# SCH_hdzero_analog_module_slim_2023-08-07.net
KiCad netlist of a schematic drawn in EasyEDA
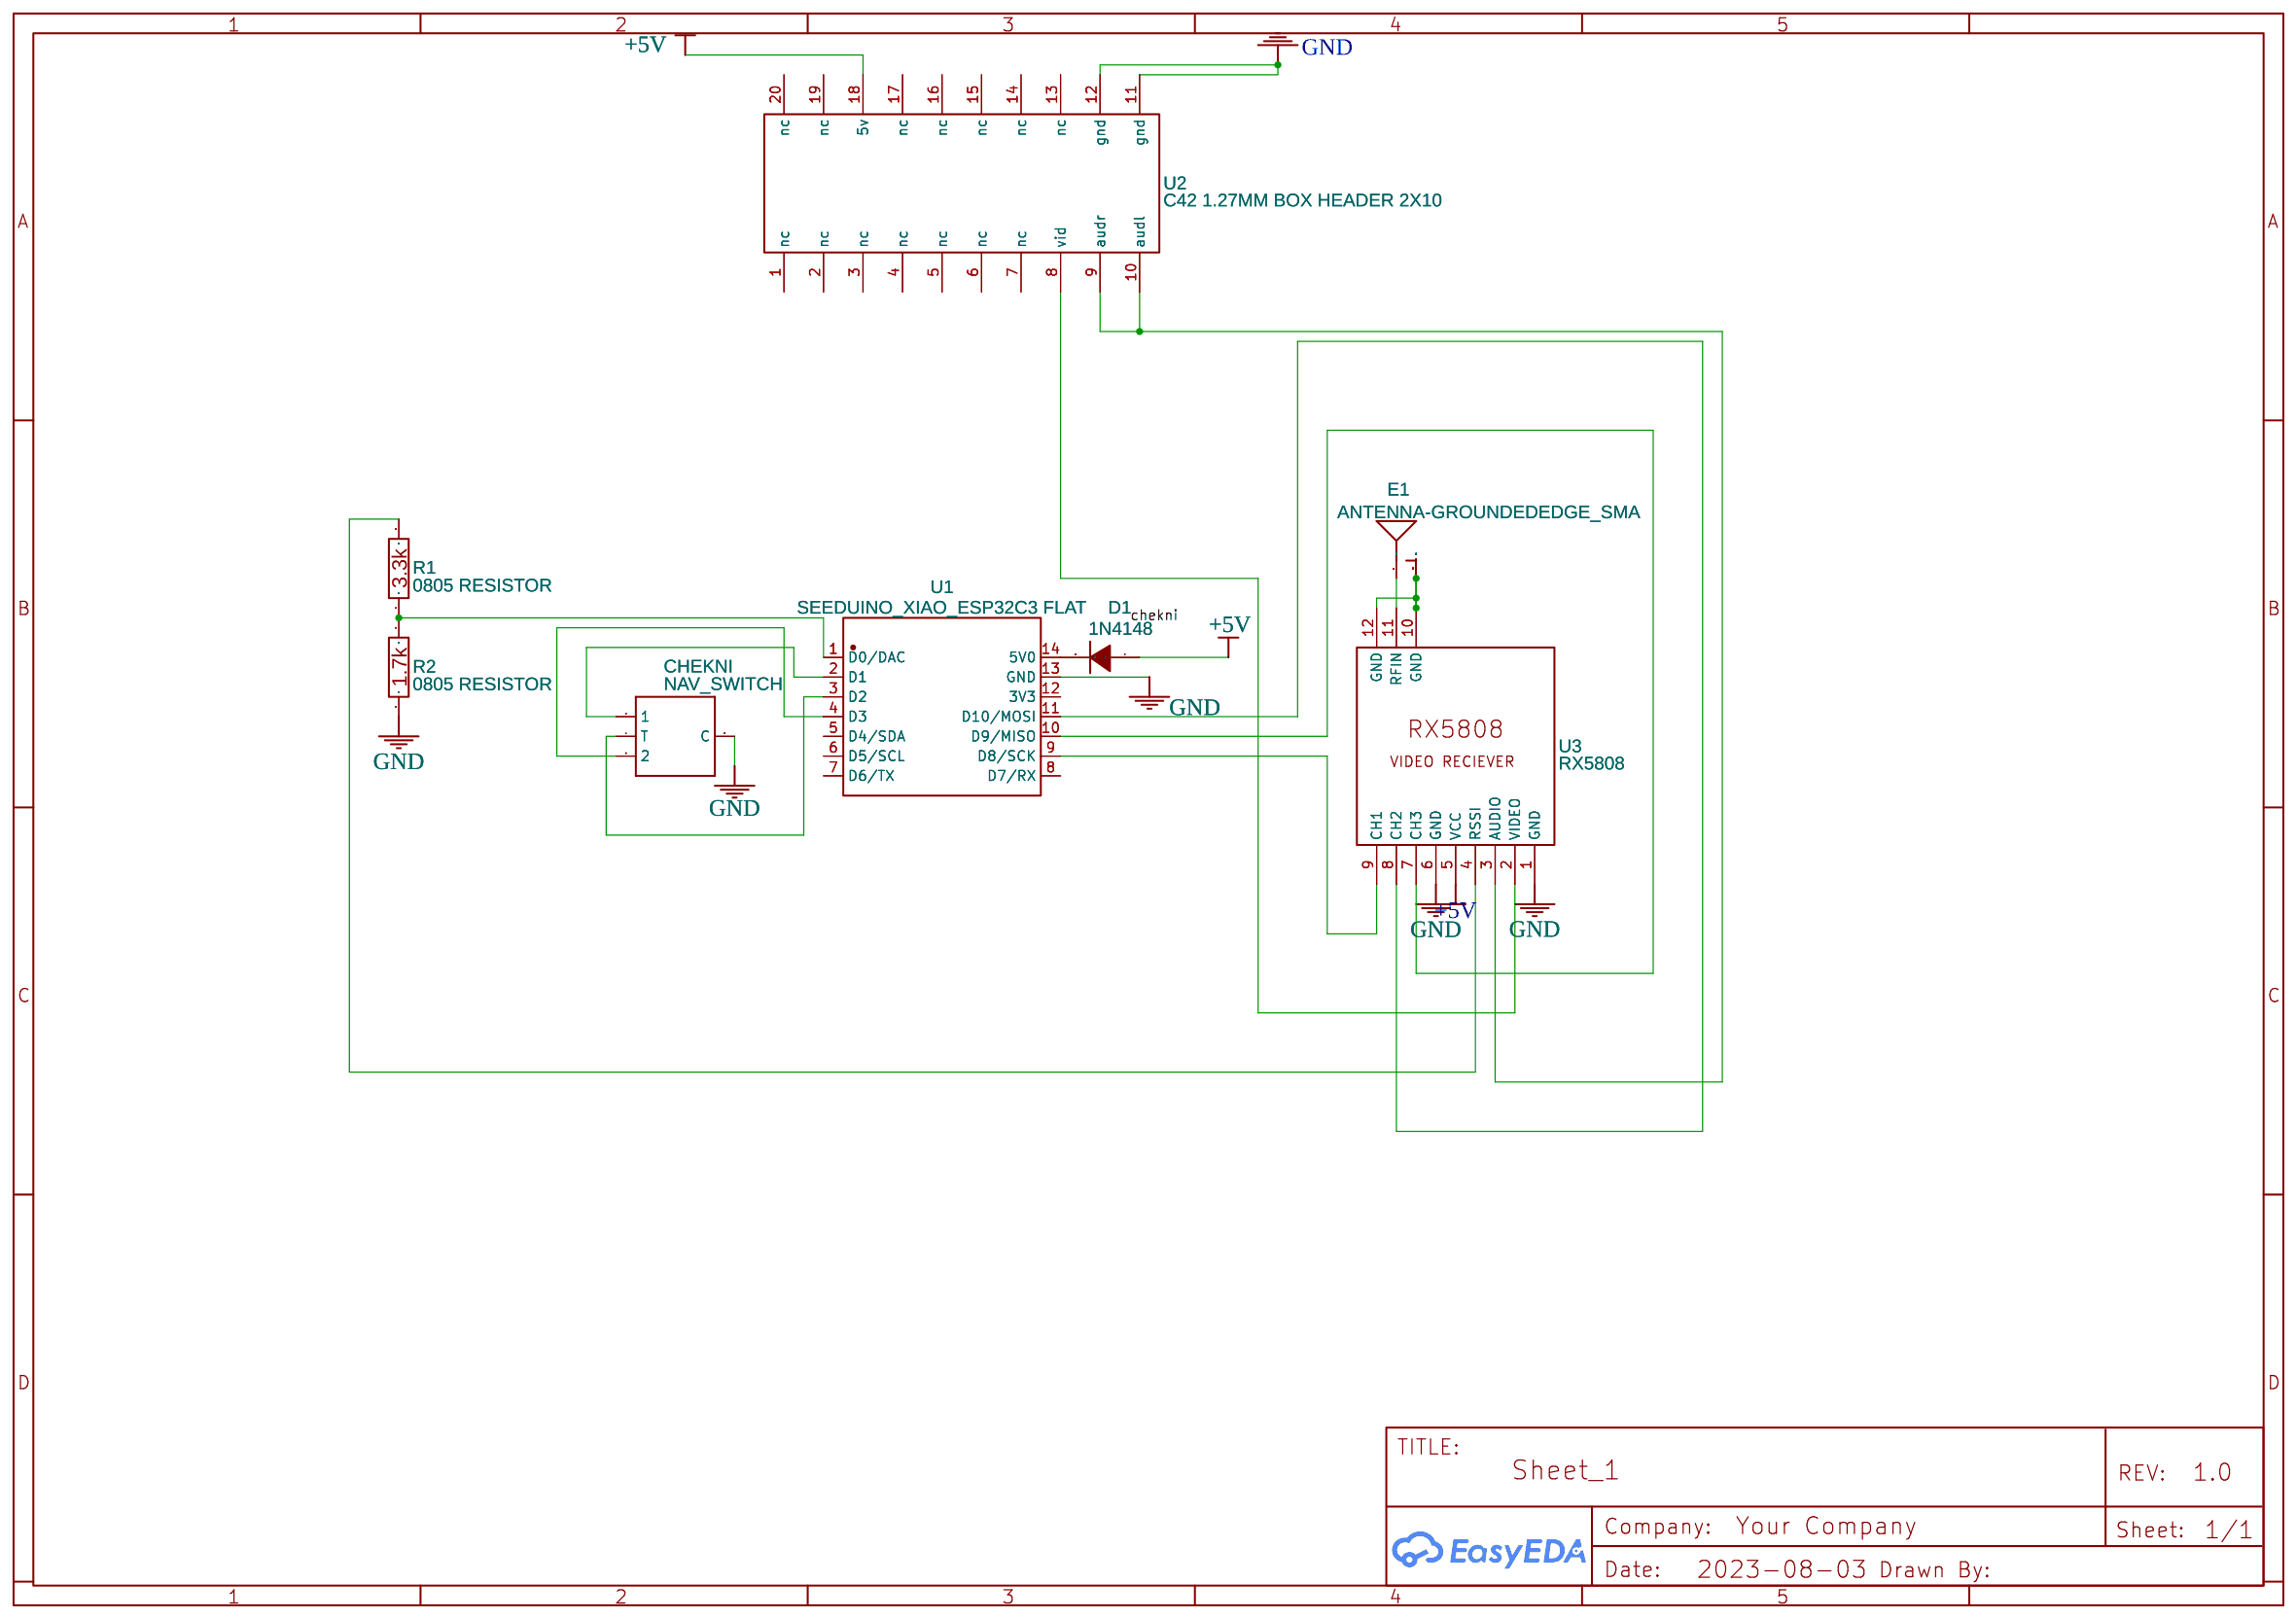
[diagram p0: schematic sheet]

(export (version "E")
  (design (tool "Eeschema 10.0.6"))
  (components
    (comp (ref "CHEKNI") (value "NAV_SWITCH") (libsource (lib "") (part "NAV_SWITCH")))
    (comp (ref "D1")
      (value "1N4148")
      (fields (field (name "Manufacturer") "ST(先科)"))
      (libsource (lib "") (part "1N4148"))
    )
    (comp (ref "E1")
      (value "ANTENNA-GROUNDEDEDGE_SMA")
      (libsource (lib "") (part "ANTENNA-GROUNDEDEDGE_RPSMA"))
    )
    (comp (ref "R1") (value "0805 RESISTOR") (libsource (lib "") (part "0805 RESISTOR_1")))
    (comp (ref "R2") (value "0805 RESISTOR") (libsource (lib "") (part "0805 RESISTOR")))
    (comp (ref "U1")
      (value "SEEDUINO_XIAO_ESP32C3 FLAT")
      (libsource (lib "") (part "SEEDUINO_XIAO_ESP32C3 FLAT"))
    )
    (comp (ref "U2")
      (value "C42 1.27MM BOX HEADER 2X10")
      (fields (field (name "BOM_Manufacturer Part") "New SchematicLib"))
      (libsource (lib "") (part "C42 1.27MM BOX HEADER 2X10"))
    )
    (comp (ref "U3") (value "RX5808") (libsource (lib "") (part "RX5808")))
  )
  (nets
    (net (code "1") (name "+5V") (class "Default")
      (node (ref "D1") (pin "1") (pinfunction "A_1") (pintype "unspecified"))
      (node (ref "U2") (pin "18") (pinfunction "5v_18") (pintype "unspecified"))
      (node (ref "U3") (pin "5") (pinfunction "VCC_5") (pintype "unspecified"))
    )
    (net (code "3") (name "GND") (class "Default")
      (node (ref "CHEKNI") (pin "C") (pinfunction "C_C") (pintype "passive"))
      (node (ref "R2") (pin "1") (pinfunction "1_1") (pintype "unspecified"))
      (node (ref "U1") (pin "13") (pinfunction "GND_13") (pintype "unspecified"))
      (node (ref "U2") (pin "11") (pinfunction "gnd_11") (pintype "unspecified"))
      (node (ref "U2") (pin "12") (pinfunction "gnd_12") (pintype "unspecified"))
      (node (ref "U3") (pin "1") (pinfunction "GND_1") (pintype "unspecified"))
      (node (ref "U3") (pin "6") (pinfunction "GND_6") (pintype "unspecified"))
    )
    (net (code "4") (name "Net-(D1-C)") (class "Default")
      (node (ref "D1") (pin "2") (pinfunction "C_2") (pintype "unspecified"))
      (node (ref "U1") (pin "14") (pinfunction "5V0_14") (pintype "unspecified"))
    )
    (net (code "5") (name "Net-(E1-GND-PadGND@0)") (class "Default")
      (node (ref "E1") (pin "GND@0") (pinfunction "GND_GND@0") (pintype "bidirectional"))
      (node (ref "E1") (pin "GND@1") (pinfunction "GND_GND@1") (pintype "bidirectional"))
      (node (ref "E1") (pin "GND@2") (pinfunction "GND_GND@2") (pintype "bidirectional"))
      (node (ref "E1") (pin "GND@3") (pinfunction "GND_GND@3") (pintype "bidirectional"))
      (node (ref "U3") (pin "10") (pinfunction "GND_10") (pintype "unspecified"))
      (node (ref "U3") (pin "12") (pinfunction "GND_12") (pintype "unspecified"))
    )
    (net (code "6") (name "Net-(E1-SIGNAL)") (class "Default")
      (node (ref "E1") (pin "SIG") (pinfunction "SIGNAL_SIG") (pintype "bidirectional"))
      (node (ref "U3") (pin "11") (pinfunction "RFIN_11") (pintype "unspecified"))
    )
    (net (code "7") (name "Net-(U1-D0{slash}DAC)") (class "Default")
      (node (ref "R1") (pin "1") (pinfunction "1_1") (pintype "unspecified"))
      (node (ref "R2") (pin "2") (pinfunction "2_2") (pintype "unspecified"))
      (node (ref "U1") (pin "1") (pinfunction "D0/DAC_1") (pintype "unspecified"))
    )
    (net (code "8") (name "Net-(U1-D1)") (class "Default")
      (node (ref "CHEKNI") (pin "1") (pinfunction "1_1") (pintype "input"))
      (node (ref "U1") (pin "2") (pinfunction "D1_2") (pintype "unspecified"))
    )
    (net (code "9") (name "Net-(U1-D2)") (class "Default")
      (node (ref "CHEKNI") (pin "T") (pinfunction "T_T") (pintype "input"))
      (node (ref "U1") (pin "3") (pinfunction "D2_3") (pintype "unspecified"))
    )
    (net (code "10") (name "Net-(U1-D3)") (class "Default")
      (node (ref "CHEKNI") (pin "2") (pinfunction "2_2") (pintype "input"))
      (node (ref "U1") (pin "4") (pinfunction "D3_4") (pintype "unspecified"))
    )
    (net (code "11") (name "Net-(U1-D8{slash}SCK)") (class "Default")
      (node (ref "U1") (pin "9") (pinfunction "D8/SCK_9") (pintype "unspecified"))
      (node (ref "U3") (pin "9") (pinfunction "CH1_9") (pintype "unspecified"))
    )
    (net (code "12") (name "Net-(U1-D9{slash}MISO)") (class "Default")
      (node (ref "U1") (pin "10") (pinfunction "D9/MISO_10") (pintype "unspecified"))
      (node (ref "U3") (pin "7") (pinfunction "CH3_7") (pintype "unspecified"))
    )
    (net (code "13") (name "Net-(U1-D10{slash}MOSI)") (class "Default")
      (node (ref "U1") (pin "11") (pinfunction "D10/MOSI_11") (pintype "unspecified"))
      (node (ref "U3") (pin "8") (pinfunction "CH2_8") (pintype "unspecified"))
    )
    (net (code "14") (name "Net-(U2-audl)") (class "Default")
      (node (ref "U2") (pin "10") (pinfunction "audl_10") (pintype "unspecified"))
      (node (ref "U2") (pin "9") (pinfunction "audr_9") (pintype "unspecified"))
      (node (ref "U3") (pin "3") (pinfunction "AUDIO_3") (pintype "unspecified"))
    )
    (net (code "15") (name "Net-(U2-vid)") (class "Default")
      (node (ref "U2") (pin "8") (pinfunction "vid_8") (pintype "unspecified"))
      (node (ref "U3") (pin "2") (pinfunction "VIDEO_2") (pintype "unspecified"))
    )
    (net (code "16") (name "Net-(U3-RSSI)") (class "Default")
      (node (ref "R1") (pin "2") (pinfunction "2_2") (pintype "unspecified"))
      (node (ref "U3") (pin "4") (pinfunction "RSSI_4") (pintype "unspecified"))
    )
    (net (code "17") (name "unconnected-(U1-3V3-Pad12)") (class "Default")
      (node (ref "U1") (pin "12") (pinfunction "3V3_12") (pintype "unspecified"))
    )
    (net (code "18") (name "unconnected-(U1-D4{slash}SDA-Pad5)") (class "Default")
      (node (ref "U1") (pin "5") (pinfunction "D4/SDA_5") (pintype "unspecified"))
    )
    (net (code "19") (name "unconnected-(U1-D5{slash}SCL-Pad6)") (class "Default")
      (node (ref "U1") (pin "6") (pinfunction "D5/SCL_6") (pintype "unspecified"))
    )
    (net (code "20") (name "unconnected-(U1-D6{slash}TX-Pad7)") (class "Default")
      (node (ref "U1") (pin "7") (pinfunction "D6/TX_7") (pintype "unspecified"))
    )
    (net (code "21") (name "unconnected-(U1-D7{slash}RX-Pad8)") (class "Default")
      (node (ref "U1") (pin "8") (pinfunction "D7/RX_8") (pintype "unspecified"))
    )
    (net (code "22") (name "unconnected-(U2-nc-Pad1)") (class "Default")
      (node (ref "U2") (pin "1") (pinfunction "nc_1") (pintype "unspecified"))
    )
    (net (code "23") (name "unconnected-(U2-nc-Pad2)") (class "Default")
      (node (ref "U2") (pin "2") (pinfunction "nc_2") (pintype "unspecified"))
    )
    (net (code "24") (name "unconnected-(U2-nc-Pad3)") (class "Default")
      (node (ref "U2") (pin "3") (pinfunction "nc_3") (pintype "unspecified"))
    )
    (net (code "25") (name "unconnected-(U2-nc-Pad4)") (class "Default")
      (node (ref "U2") (pin "4") (pinfunction "nc_4") (pintype "unspecified"))
    )
    (net (code "26") (name "unconnected-(U2-nc-Pad5)") (class "Default")
      (node (ref "U2") (pin "5") (pinfunction "nc_5") (pintype "unspecified"))
    )
    (net (code "27") (name "unconnected-(U2-nc-Pad6)") (class "Default")
      (node (ref "U2") (pin "6") (pinfunction "nc_6") (pintype "unspecified"))
    )
    (net (code "28") (name "unconnected-(U2-nc-Pad7)") (class "Default")
      (node (ref "U2") (pin "7") (pinfunction "nc_7") (pintype "unspecified"))
    )
    (net (code "29") (name "unconnected-(U2-nc-Pad13)") (class "Default")
      (node (ref "U2") (pin "13") (pinfunction "nc_13") (pintype "unspecified"))
    )
    (net (code "30") (name "unconnected-(U2-nc-Pad14)") (class "Default")
      (node (ref "U2") (pin "14") (pinfunction "nc_14") (pintype "unspecified"))
    )
    (net (code "31") (name "unconnected-(U2-nc-Pad15)") (class "Default")
      (node (ref "U2") (pin "15") (pinfunction "nc_15") (pintype "unspecified"))
    )
    (net (code "32") (name "unconnected-(U2-nc-Pad16)") (class "Default")
      (node (ref "U2") (pin "16") (pinfunction "nc_16") (pintype "unspecified"))
    )
    (net (code "33") (name "unconnected-(U2-nc-Pad17)") (class "Default")
      (node (ref "U2") (pin "17") (pinfunction "nc_17") (pintype "unspecified"))
    )
    (net (code "34") (name "unconnected-(U2-nc-Pad19)") (class "Default")
      (node (ref "U2") (pin "19") (pinfunction "nc_19") (pintype "unspecified"))
    )
    (net (code "35") (name "unconnected-(U2-nc-Pad20)") (class "Default")
      (node (ref "U2") (pin "20") (pinfunction "nc_20") (pintype "unspecified"))
    )
  )
)
